# bi1r7.net
KiCad netlist of a schematic drawn in EAGLE
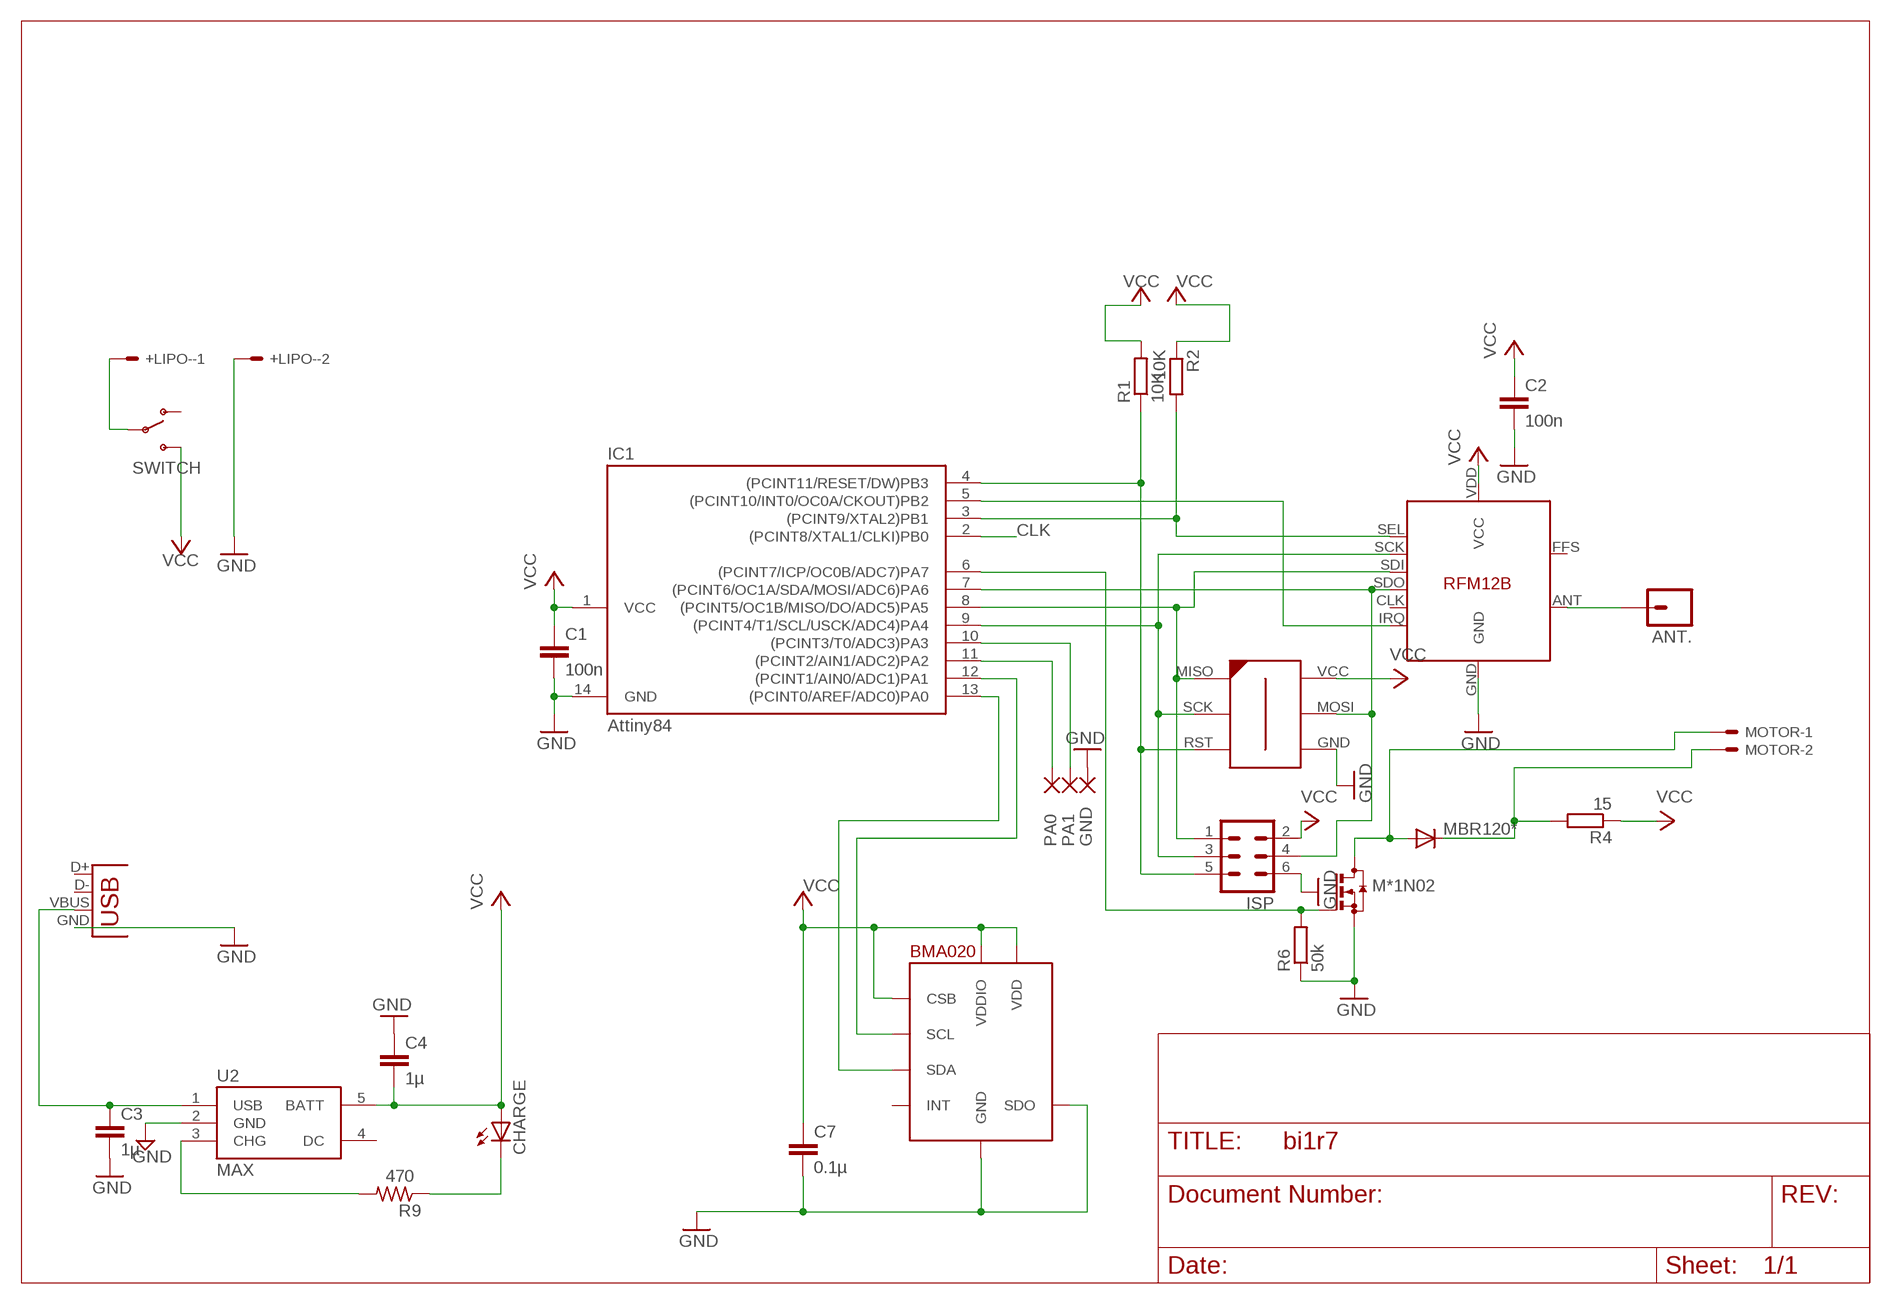
[diagram p0: schematic, sheet 1]

(export (version "E")
  (design (tool "Eeschema 10.0.6"))
  (components
    (comp (ref "+LIPO-")
      (value "SM02B-SRSS-TB")
      (footprint "eagle-import:SM02B-SRSS-TB")
      (libsource (lib "eagle-import") (part "?M02B-SRSS-TBS"))
    )
    (comp (ref "ANT.")
      (value "M01PTH")
      (footprint "eagle-import:1X01")
      (libsource (lib "eagle-import") (part "M01PTH"))
    )
    (comp (ref "BMA020")
      (value "BMA020")
      (footprint "eagle-import:LBA-12")
      (libsource (lib "eagle-import") (part "BMA020"))
    )
    (comp (ref "C1")
      (value "100n")
      (footprint "eagle-import:C0603K")
      (libsource (lib "eagle-import") (part "C-EUC0603K"))
    )
    (comp (ref "C2")
      (value "100n")
      (footprint "eagle-import:C0603K")
      (libsource (lib "eagle-import") (part "C-EUC0603K"))
    )
    (comp (ref "C3")
      (value "1µ")
      (footprint "eagle-import:0603-CAP")
      (libsource (lib "eagle-import") (part "CAP0603-CAP"))
    )
    (comp (ref "C4")
      (value "1µ")
      (footprint "eagle-import:0603-CAP")
      (libsource (lib "eagle-import") (part "CAP0603-CAP"))
    )
    (comp (ref "C7")
      (value "0.1µ")
      (footprint "eagle-import:0603-CAP")
      (libsource (lib "eagle-import") (part "CAP0603-CAP"))
    )
    (comp (ref "CHARGE")
      (value "LED0603")
      (footprint "eagle-import:LED-0603")
      (libsource (lib "eagle-import") (part "LED0603"))
    )
    (comp (ref "GND")
      (value "SMD2")
      (footprint "eagle-import:SMD1,27-2,54")
      (libsource (lib "eagle-import") (part "SMD2"))
    )
    (comp (ref "IC1")
      (value "Attiny84")
      (footprint "eagle-import:SOIC14")
      (libsource (lib "eagle-import") (part "TINY24/44/84-SSU"))
    )
    (comp (ref "ISP")
      (value "MA03-2S")
      (footprint "eagle-import:MA03-2-0.8")
      (libsource (lib "eagle-import") (part "MA03-2S"))
    )
    (comp (ref "M*1N02")
      (value "BSS123")
      (footprint "eagle-import:SOT23")
      (libsource (lib "eagle-import") (part "BSS123"))
    )
    (comp (ref "MBR120*")
      (value "CGRM4001-G")
      (footprint "eagle-import:SOD-123_MINI-SMA")
      (libsource (lib "eagle-import") (part "CGRM400-G1"))
    )
    (comp (ref "MOTOR")
      (value "SM02B-SRSS-TB")
      (footprint "eagle-import:SM02B-SRSS-TB")
      (libsource (lib "eagle-import") (part "?M02B-SRSS-TBS"))
    )
    (comp (ref "PA0")
      (value "SMD2")
      (footprint "eagle-import:SMD1,27-2,54")
      (libsource (lib "eagle-import") (part "SMD2"))
    )
    (comp (ref "PA1")
      (value "SMD2")
      (footprint "eagle-import:SMD1,27-2,54")
      (libsource (lib "eagle-import") (part "SMD2"))
    )
    (comp (ref "R1")
      (value "10K")
      (footprint "eagle-import:R0603")
      (libsource (lib "eagle-import") (part "R-EU_R0603"))
    )
    (comp (ref "R2")
      (value "10K")
      (footprint "eagle-import:R0603")
      (libsource (lib "eagle-import") (part "R-EU_R0603"))
    )
    (comp (ref "R4")
      (value "15")
      (footprint "eagle-import:R0603")
      (libsource (lib "eagle-import") (part "R-EU_R0603"))
    )
    (comp (ref "R6")
      (value "50k")
      (footprint "eagle-import:R0603")
      (libsource (lib "eagle-import") (part "R-EU_R0603"))
    )
    (comp (ref "R9")
      (value "470")
      (footprint "eagle-import:R0603")
      (libsource (lib "eagle-import") (part "R-US_R0603"))
    )
    (comp (ref "RFM12B")
      (value "RFM12B")
      (footprint "eagle-import:RFM12B")
      (libsource (lib "eagle-import") (part "RFM12B"))
    )
    (comp (ref "SWITCH")
      (value "SWITCH-SPDTSMD2")
      (footprint "eagle-import:SWITCH-SPDT-SMD")
      (libsource (lib "eagle-import") (part "SWITCH-SPDTSMD2"))
    )
    (comp (ref "U$2")
      (value "AVR-ISP-6-EDGE")
      (footprint "eagle-import:6PAD_ISP")
      (libsource (lib "eagle-import") (part "AVR-ISP-6-EDGE"))
    )
    (comp (ref "U2")
      (value "MAX")
      (footprint "eagle-import:SOT23-5")
      (libsource (lib "eagle-import") (part "MAX1555"))
    )
    (comp (ref "USB")
      (value "USB-MICROB")
      (footprint "eagle-import:USB-MICROB")
      (libsource (lib "eagle-import") (part "USB-MICROB"))
    )
  )
  (nets
    (net (code "1") (name "/CLK") (class "Default")
      (node (ref "IC1") (pin "2") (pinfunction "(PCINT8/XTAL1/CLKI)PB0_2") (pintype "bidirectional"))
    )
    (net (code "2") (name "GND") (class "Default")
      (node (ref "+LIPO-") (pin "2") (pinfunction "S_2") (pintype "passive"))
      (node (ref "BMA020") (pin "P$3") (pinfunction "GND_P$3") (pintype "power_in"))
      (node (ref "BMA020") (pin "P$7") (pinfunction "SDO_P$7") (pintype "bidirectional"))
      (node (ref "C1") (pin "2") (pinfunction "2_2") (pintype "passive"))
      (node (ref "C2") (pin "2") (pinfunction "2_2") (pintype "passive"))
      (node (ref "C3") (pin "2") (pinfunction "2_2") (pintype "passive"))
      (node (ref "C4") (pin "1") (pinfunction "1_1") (pintype "passive"))
      (node (ref "C7") (pin "2") (pinfunction "2_2") (pintype "passive"))
      (node (ref "GND") (pin "1") (pinfunction "P_1") (pintype "passive"))
      (node (ref "IC1") (pin "14") (pinfunction "GND_14") (pintype "power_in"))
      (node (ref "ISP") (pin "6") (pinfunction "6_6") (pintype "passive"))
      (node (ref "M*1N02") (pin "2") (pinfunction "S_2") (pintype "passive"))
      (node (ref "R6") (pin "1") (pinfunction "1_1") (pintype "passive"))
      (node (ref "RFM12B") (pin "GND") (pinfunction "GND_GND") (pintype "power_in"))
      (node (ref "U$2") (pin "GND") (pinfunction "P$4_GND") (pintype "bidirectional"))
      (node (ref "U2") (pin "2") (pinfunction "GND_2") (pintype "bidirectional"))
      (node (ref "USB") (pin "GND") (pinfunction "GND_GND") (pintype "bidirectional"))
    )
    (net (code "3") (name "Net-(+LIPO-A-S)") (class "Default")
      (node (ref "+LIPO-") (pin "1") (pinfunction "S_1") (pintype "passive"))
      (node (ref "SWITCH") (pin "2") (pinfunction "P_2") (pintype "passive"))
    )
    (net (code "4") (name "Net-(ANT.-Pad1)") (class "Default")
      (node (ref "ANT.") (pin "1") (pinfunction "1_1") (pintype "passive"))
      (node (ref "RFM12B") (pin "ANT") (pinfunction "ANT_ANT") (pintype "passive"))
    )
    (net (code "5") (name "Net-(BMA020-SCL)") (class "Default")
      (node (ref "BMA020") (pin "P$6") (pinfunction "SCL_P$6") (pintype "bidirectional"))
      (node (ref "IC1") (pin "12") (pinfunction "(PCINT1/AIN0/ADC1)PA1_12") (pintype "bidirectional"))
    )
    (net (code "6") (name "Net-(BMA020-SDA)") (class "Default")
      (node (ref "BMA020") (pin "P$8") (pinfunction "SDA_P$8") (pintype "bidirectional"))
      (node (ref "IC1") (pin "13") (pinfunction "(PCINT0/AREF/ADC0)PA0_13") (pintype "bidirectional"))
    )
    (net (code "7") (name "Net-(CHARGE-PadC)") (class "Default")
      (node (ref "CHARGE") (pin "C") (pinfunction "C_C") (pintype "passive"))
      (node (ref "R9") (pin "1") (pinfunction "1_1") (pintype "passive"))
    )
    (net (code "8") (name "Net-(IC1-(PCINT2{slash}AIN1{slash}ADC2)PA2)") (class "Default")
      (node (ref "IC1") (pin "11") (pinfunction "(PCINT2/AIN1/ADC2)PA2_11") (pintype "bidirectional"))
      (node (ref "PA0") (pin "1") (pinfunction "P_1") (pintype "passive"))
    )
    (net (code "9") (name "Net-(IC1-(PCINT3{slash}T0{slash}ADC3)PA3)") (class "Default")
      (node (ref "IC1") (pin "10") (pinfunction "(PCINT3/T0/ADC3)PA3_10") (pintype "bidirectional"))
      (node (ref "PA1") (pin "1") (pinfunction "P_1") (pintype "passive"))
    )
    (net (code "10") (name "Net-(IC1-(PCINT4{slash}T1{slash}SCL{slash}USCK{slash}ADC4)PA4)") (class "Default")
      (node (ref "IC1") (pin "9") (pinfunction "(PCINT4/T1/SCL/USCK/ADC4)PA4_9") (pintype "bidirectional"))
      (node (ref "ISP") (pin "3") (pinfunction "3_3") (pintype "passive"))
      (node (ref "RFM12B") (pin "SCK") (pinfunction "SCK_SCK") (pintype "input"))
      (node (ref "U$2") (pin "SCK") (pinfunction "P$2_SCK") (pintype "bidirectional"))
    )
    (net (code "11") (name "Net-(IC1-(PCINT5{slash}OC1B{slash}MISO{slash}DO{slash}ADC5)PA5)") (class "Default")
      (node (ref "IC1") (pin "8") (pinfunction "(PCINT5/OC1B/MISO/DO/ADC5)PA5_8") (pintype "bidirectional"))
      (node (ref "ISP") (pin "1") (pinfunction "1_1") (pintype "passive"))
      (node (ref "RFM12B") (pin "SDI") (pinfunction "SDI_SDI") (pintype "input"))
      (node (ref "U$2") (pin "MISO") (pinfunction "P$1_MISO") (pintype "bidirectional"))
    )
    (net (code "12") (name "Net-(IC1-(PCINT6{slash}OC1A{slash}SDA{slash}MOSI{slash}ADC6)PA6)") (class "Default")
      (node (ref "IC1") (pin "7") (pinfunction "(PCINT6/OC1A/SDA/MOSI/ADC6)PA6_7") (pintype "bidirectional"))
      (node (ref "ISP") (pin "4") (pinfunction "4_4") (pintype "passive"))
      (node (ref "RFM12B") (pin "SDO") (pinfunction "SDO_SDO") (pintype "output"))
      (node (ref "U$2") (pin "MOSI") (pinfunction "P$5_MOSI") (pintype "bidirectional"))
    )
    (net (code "13") (name "Net-(IC1-(PCINT7{slash}ICP{slash}OC0B{slash}ADC7)PA7)") (class "Default")
      (node (ref "IC1") (pin "6") (pinfunction "(PCINT7/ICP/OC0B/ADC7)PA7_6") (pintype "bidirectional"))
      (node (ref "M*1N02") (pin "1") (pinfunction "G_1") (pintype "passive"))
      (node (ref "R6") (pin "2") (pinfunction "2_2") (pintype "passive"))
    )
    (net (code "14") (name "Net-(IC1-(PCINT9{slash}XTAL2)PB1)") (class "Default")
      (node (ref "IC1") (pin "3") (pinfunction "(PCINT9/XTAL2)PB1_3") (pintype "bidirectional"))
      (node (ref "R2") (pin "2") (pinfunction "2_2") (pintype "passive"))
      (node (ref "RFM12B") (pin "SEL") (pinfunction "SEL_SEL") (pintype "input"))
    )
    (net (code "15") (name "Net-(IC1-(PCINT10{slash}INT0{slash}OC0A{slash}CKOUT)PB2)") (class "Default")
      (node (ref "IC1") (pin "5") (pinfunction "(PCINT10/INT0/OC0A/CKOUT)PB2_5") (pintype "bidirectional"))
      (node (ref "RFM12B") (pin "IRQ") (pinfunction "IRQ_IRQ") (pintype "open_collector"))
    )
    (net (code "16") (name "Net-(IC1-(PCINT11{slash}RESET{slash}DW)PB3)") (class "Default")
      (node (ref "IC1") (pin "4") (pinfunction "(PCINT11/RESET/DW)PB3_4") (pintype "bidirectional"))
      (node (ref "ISP") (pin "5") (pinfunction "5_5") (pintype "passive"))
      (node (ref "R1") (pin "1") (pinfunction "1_1") (pintype "passive"))
      (node (ref "U$2") (pin "RST") (pinfunction "P$3_RST") (pintype "bidirectional"))
    )
    (net (code "17") (name "Net-(M*1N02-D)") (class "Default")
      (node (ref "M*1N02") (pin "3") (pinfunction "D_3") (pintype "passive"))
      (node (ref "MBR120*") (pin "A") (pinfunction "A_A") (pintype "passive"))
      (node (ref "MOTOR") (pin "1") (pinfunction "S_1") (pintype "passive"))
    )
    (net (code "18") (name "Net-(MOTORB-S)") (class "Default")
      (node (ref "MBR120*") (pin "C") (pinfunction "C_C") (pintype "passive"))
      (node (ref "MOTOR") (pin "2") (pinfunction "S_2") (pintype "passive"))
      (node (ref "R4") (pin "2") (pinfunction "2_2") (pintype "passive"))
    )
    (net (code "19") (name "Net-(U2-CHG)") (class "Default")
      (node (ref "R9") (pin "2") (pinfunction "2_2") (pintype "passive"))
      (node (ref "U2") (pin "3") (pinfunction "CHG_3") (pintype "bidirectional"))
    )
    (net (code "20") (name "Net-(U2-USB)") (class "Default")
      (node (ref "C3") (pin "1") (pinfunction "1_1") (pintype "passive"))
      (node (ref "U2") (pin "1") (pinfunction "USB_1") (pintype "bidirectional"))
      (node (ref "USB") (pin "VBUS") (pinfunction "VBUS_VBUS") (pintype "bidirectional"))
    )
    (net (code "21") (name "VCC") (class "Default")
      (node (ref "BMA020") (pin "P$2") (pinfunction "VDD_P$2") (pintype "power_in"))
      (node (ref "BMA020") (pin "P$5") (pinfunction "CSB_P$5") (pintype "bidirectional"))
      (node (ref "BMA020") (pin "P$9") (pinfunction "VDDIO_P$9") (pintype "power_in"))
      (node (ref "C1") (pin "1") (pinfunction "1_1") (pintype "passive"))
      (node (ref "C2") (pin "1") (pinfunction "1_1") (pintype "passive"))
      (node (ref "C4") (pin "2") (pinfunction "2_2") (pintype "passive"))
      (node (ref "C7") (pin "1") (pinfunction "1_1") (pintype "passive"))
      (node (ref "CHARGE") (pin "A") (pinfunction "A_A") (pintype "passive"))
      (node (ref "IC1") (pin "1") (pinfunction "VCC_1") (pintype "power_in"))
      (node (ref "ISP") (pin "2") (pinfunction "2_2") (pintype "passive"))
      (node (ref "R1") (pin "2") (pinfunction "2_2") (pintype "passive"))
      (node (ref "R2") (pin "1") (pinfunction "1_1") (pintype "passive"))
      (node (ref "R4") (pin "1") (pinfunction "1_1") (pintype "passive"))
      (node (ref "RFM12B") (pin "VDD") (pinfunction "VCC_VDD") (pintype "power_in"))
      (node (ref "SWITCH") (pin "3") (pinfunction "S_3") (pintype "passive"))
      (node (ref "U$2") (pin "VCC") (pinfunction "P$6_VCC") (pintype "bidirectional"))
      (node (ref "U2") (pin "5") (pinfunction "BATT_5") (pintype "bidirectional"))
    )
    (net (code "22") (name "unconnected-(BMA020-INT-PadP$4)") (class "Default")
      (node (ref "BMA020") (pin "P$4") (pinfunction "INT_P$4") (pintype "open_collector"))
    )
    (net (code "23") (name "unconnected-(RFM12B-PadCLK)") (class "Default")
      (node (ref "RFM12B") (pin "CLK") (pinfunction "CLK_CLK") (pintype "output"))
    )
    (net (code "24") (name "unconnected-(RFM12B-PadFFS)") (class "Default")
      (node (ref "RFM12B") (pin "FFS") (pinfunction "FFS_FFS") (pintype "bidirectional"))
    )
    (net (code "25") (name "unconnected-(SWITCH-O-Pad1)") (class "Default")
      (node (ref "SWITCH") (pin "1") (pinfunction "O_1") (pintype "passive"))
    )
    (net (code "26") (name "unconnected-(U2-DC-Pad4)") (class "Default")
      (node (ref "U2") (pin "4") (pinfunction "DC_4") (pintype "bidirectional"))
    )
    (net (code "27") (name "unconnected-(USB-PadD+)") (class "Default")
      (node (ref "USB") (pin "D+") (pinfunction "D+_D+") (pintype "bidirectional"))
    )
    (net (code "28") (name "unconnected-(USB-PadD-)") (class "Default")
      (node (ref "USB") (pin "D-") (pinfunction "D-_D-") (pintype "bidirectional"))
    )
  )
)
